# Antenna_Board_v4.net
KiCad netlist of a schematic drawn in EAGLE
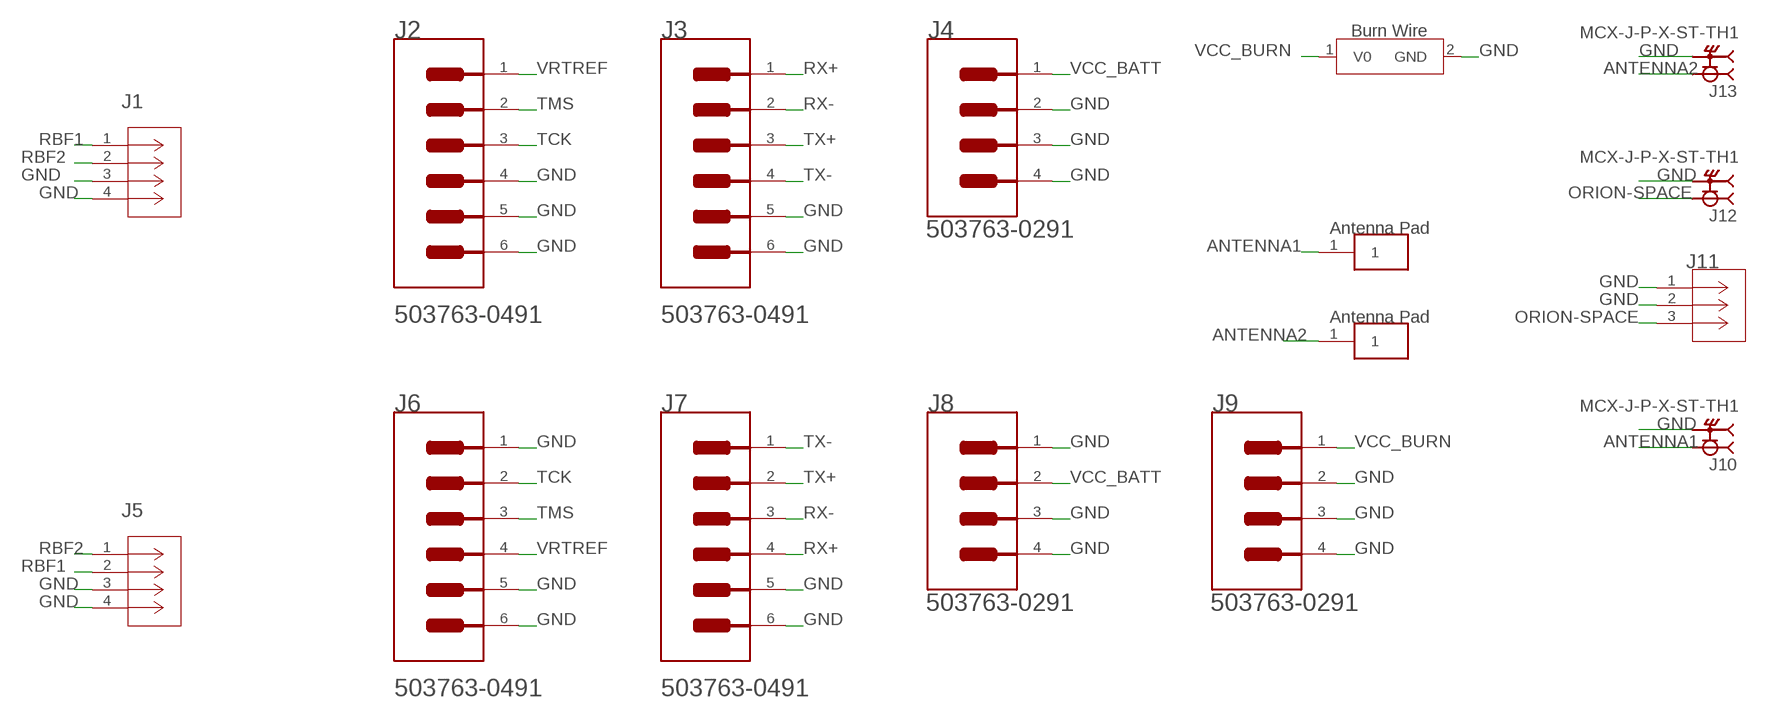
[diagram p0: schematic, sheet 1]

(export (version "E")
  (design (tool "Eeschema 10.0.6"))
  (components
    (comp (ref "J1")
      (value "5037630291")
      (footprint "eagle-import:CON_5037630291")
      (fields (field (name "COPYRIGHT") "Copyright (C) 2018 Accelerated Designs. All rights reserved"))
      (libsource (lib "eagle-import") (part "5037630291"))
    )
    (comp (ref "J2")
      (value "MOLEX_503763-0491MOLEX_503763-0491_0_0")
      (footprint "eagle-import:MOLEX_503763-0491_0")
      (fields
        (field (name "DIGIKEY_PART_NUMBER") "WM10655CT-ND")
        (field (name "MF") "Molex")
        (field (name "MOUSER_PART_NUMBER") "538-503763-0491")
      )
      (libsource (lib "eagle-import") (part "MOLEX_503763-0491MOLEX_503763-0491_0_0"))
    )
    (comp (ref "J3")
      (value "MOLEX_503763-0491MOLEX_503763-0491_0_0")
      (footprint "eagle-import:MOLEX_503763-0491_0")
      (fields
        (field (name "DIGIKEY_PART_NUMBER") "WM10655CT-ND")
        (field (name "MF") "Molex")
        (field (name "MOUSER_PART_NUMBER") "538-503763-0491")
      )
      (libsource (lib "eagle-import") (part "MOLEX_503763-0491MOLEX_503763-0491_0_0"))
    )
    (comp (ref "J4")
      (value "MOLEX_503763-0291MOLEX_503763-0291_0_0")
      (footprint "eagle-import:MOLEX_503763-0291_0")
      (fields
        (field (name "DIGIKEY_PART_NUMBER") "WM10654CT-ND")
        (field (name "MF") "Molex")
        (field (name "MOUSER_PART_NUMBER") "538-503763-0291")
      )
      (libsource (lib "eagle-import") (part "MOLEX_503763-0291MOLEX_503763-0291_0_0"))
    )
    (comp (ref "J5")
      (value "5037630291")
      (footprint "eagle-import:CON_5037630291")
      (fields (field (name "COPYRIGHT") "Copyright (C) 2018 Accelerated Designs. All rights reserved"))
      (libsource (lib "eagle-import") (part "5037630291"))
    )
    (comp (ref "J6")
      (value "MOLEX_503763-0491MOLEX_503763-0491_0_0")
      (footprint "eagle-import:MOLEX_503763-0491_0")
      (fields
        (field (name "DIGIKEY_PART_NUMBER") "WM10655CT-ND")
        (field (name "MF") "Molex")
        (field (name "MOUSER_PART_NUMBER") "538-503763-0491")
      )
      (libsource (lib "eagle-import") (part "MOLEX_503763-0491MOLEX_503763-0491_0_0"))
    )
    (comp (ref "J7")
      (value "MOLEX_503763-0491MOLEX_503763-0491_0_0")
      (footprint "eagle-import:MOLEX_503763-0491_0")
      (fields
        (field (name "DIGIKEY_PART_NUMBER") "WM10655CT-ND")
        (field (name "MF") "Molex")
        (field (name "MOUSER_PART_NUMBER") "538-503763-0491")
      )
      (libsource (lib "eagle-import") (part "MOLEX_503763-0491MOLEX_503763-0491_0_0"))
    )
    (comp (ref "J8")
      (value "MOLEX_503763-0291MOLEX_503763-0291_0_0")
      (footprint "eagle-import:MOLEX_503763-0291_0")
      (fields
        (field (name "DIGIKEY_PART_NUMBER") "WM10654CT-ND")
        (field (name "MF") "Molex")
        (field (name "MOUSER_PART_NUMBER") "538-503763-0291")
      )
      (libsource (lib "eagle-import") (part "MOLEX_503763-0291MOLEX_503763-0291_0_0"))
    )
    (comp (ref "J9")
      (value "MOLEX_503763-0291MOLEX_503763-0291_0_0")
      (footprint "eagle-import:MOLEX_503763-0291_0")
      (fields
        (field (name "DIGIKEY_PART_NUMBER") "WM10654CT-ND")
        (field (name "MF") "Molex")
        (field (name "MOUSER_PART_NUMBER") "538-503763-0291")
      )
      (libsource (lib "eagle-import") (part "MOLEX_503763-0291MOLEX_503763-0291_0_0"))
    )
    (comp (ref "J10")
      (value "MCX-J-P-X-ST-TH1")
      (footprint "eagle-import:SAMTEC_MCX-J-P-X-ST-TH1")
      (fields
        (field (name "DIGI-KEY_PART_NUMBER") "SAM8944-ND")
        (field (name "MF") "Samtec")
        (field (name "MP") "MCX-J-P-H-ST-TH1")
      )
      (libsource (lib "eagle-import") (part "MCX-J-P-X-ST-TH1"))
    )
    (comp (ref "J11")
      (value "U.FL-R-SMT-1(01)")
      (footprint "eagle-import:CONN_-SMT-1(01)")
      (fields (field (name "COPYRIGHT") "Copyright (C) 2018 Accelerated Designs. All rights reserved"))
      (libsource (lib "eagle-import") (part "U.FL-R-SMT-1(01)"))
    )
    (comp (ref "J12")
      (value "MCX-J-P-X-ST-TH1")
      (footprint "eagle-import:SAMTEC_MCX-J-P-X-ST-TH1")
      (fields
        (field (name "DIGI-KEY_PART_NUMBER") "SAM8944-ND")
        (field (name "MF") "Samtec")
        (field (name "MP") "MCX-J-P-H-ST-TH1")
      )
      (libsource (lib "eagle-import") (part "MCX-J-P-X-ST-TH1"))
    )
    (comp (ref "J13")
      (value "MCX-J-P-X-ST-TH1")
      (footprint "eagle-import:SAMTEC_MCX-J-P-X-ST-TH1")
      (fields
        (field (name "DIGI-KEY_PART_NUMBER") "SAM8944-ND")
        (field (name "MF") "Samtec")
        (field (name "MP") "MCX-J-P-H-ST-TH1")
      )
      (libsource (lib "eagle-import") (part "MCX-J-P-X-ST-TH1"))
    )
    (comp (ref "U$1")
      (value "ANTENNA_PAD+HOLES")
      (footprint "eagle-import:ANTENNA_PAD+HOLES")
      (libsource (lib "eagle-import") (part "ANTENNA_PAD+HOLES"))
    )
    (comp (ref "U$2")
      (value "ANTENNA_PAD+HOLES")
      (footprint "eagle-import:ANTENNA_PAD+HOLES")
      (libsource (lib "eagle-import") (part "ANTENNA_PAD+HOLES"))
    )
    (comp (ref "U$3")
      (value "BURNWIRE")
      (footprint "eagle-import:BURNWIRE")
      (libsource (lib "eagle-import") (part "BURNWIRE"))
    )
  )
  (nets
    (net (code "1") (name "/ANTENNA1") (class "Default")
      (node (ref "J10") (pin "1") (pinfunction "1_1") (pintype "passive"))
      (node (ref "U$1") (pin "1") (pinfunction "1_1") (pintype "bidirectional"))
    )
    (net (code "2") (name "/ANTENNA2") (class "Default")
      (node (ref "J13") (pin "1") (pinfunction "1_1") (pintype "passive"))
      (node (ref "U$2") (pin "1") (pinfunction "1_1") (pintype "bidirectional"))
    )
    (net (code "3") (name "/GND") (class "Default")
      (node (ref "J1") (pin "3") (pinfunction "3_3") (pintype "passive"))
      (node (ref "J1") (pin "4") (pinfunction "4_4") (pintype "passive"))
      (node (ref "J10") (pin "S1") (pinfunction "2_S1") (pintype "passive"))
      (node (ref "J10") (pin "S2") (pinfunction "2_S2") (pintype "passive"))
      (node (ref "J10") (pin "S3") (pinfunction "2_S3") (pintype "passive"))
      (node (ref "J10") (pin "S4") (pinfunction "2_S4") (pintype "passive"))
      (node (ref "J11") (pin "1") (pinfunction "1_1") (pintype "passive"))
      (node (ref "J11") (pin "2") (pinfunction "2_2") (pintype "passive"))
      (node (ref "J12") (pin "S1") (pinfunction "2_S1") (pintype "passive"))
      (node (ref "J12") (pin "S2") (pinfunction "2_S2") (pintype "passive"))
      (node (ref "J12") (pin "S3") (pinfunction "2_S3") (pintype "passive"))
      (node (ref "J12") (pin "S4") (pinfunction "2_S4") (pintype "passive"))
      (node (ref "J13") (pin "S1") (pinfunction "2_S1") (pintype "passive"))
      (node (ref "J13") (pin "S2") (pinfunction "2_S2") (pintype "passive"))
      (node (ref "J13") (pin "S3") (pinfunction "2_S3") (pintype "passive"))
      (node (ref "J13") (pin "S4") (pinfunction "2_S4") (pintype "passive"))
      (node (ref "J2") (pin "4") (pinfunction "4_4") (pintype "passive"))
      (node (ref "J2") (pin "5") (pinfunction "MNT_1_5") (pintype "passive"))
      (node (ref "J2") (pin "6") (pinfunction "MNT_2_6") (pintype "passive"))
      (node (ref "J3") (pin "5") (pinfunction "MNT_1_5") (pintype "passive"))
      (node (ref "J3") (pin "6") (pinfunction "MNT_2_6") (pintype "passive"))
      (node (ref "J4") (pin "2") (pinfunction "2_2") (pintype "bidirectional"))
      (node (ref "J4") (pin "3") (pinfunction "MNT_1_3") (pintype "bidirectional"))
      (node (ref "J4") (pin "4") (pinfunction "MNT_2_4") (pintype "bidirectional"))
      (node (ref "J5") (pin "3") (pinfunction "3_3") (pintype "passive"))
      (node (ref "J5") (pin "4") (pinfunction "4_4") (pintype "passive"))
      (node (ref "J6") (pin "1") (pinfunction "1_1") (pintype "passive"))
      (node (ref "J6") (pin "5") (pinfunction "MNT_1_5") (pintype "passive"))
      (node (ref "J6") (pin "6") (pinfunction "MNT_2_6") (pintype "passive"))
      (node (ref "J7") (pin "5") (pinfunction "MNT_1_5") (pintype "passive"))
      (node (ref "J7") (pin "6") (pinfunction "MNT_2_6") (pintype "passive"))
      (node (ref "J8") (pin "1") (pinfunction "1_1") (pintype "bidirectional"))
      (node (ref "J8") (pin "3") (pinfunction "MNT_1_3") (pintype "bidirectional"))
      (node (ref "J8") (pin "4") (pinfunction "MNT_2_4") (pintype "bidirectional"))
      (node (ref "J9") (pin "2") (pinfunction "2_2") (pintype "bidirectional"))
      (node (ref "J9") (pin "3") (pinfunction "MNT_1_3") (pintype "bidirectional"))
      (node (ref "J9") (pin "4") (pinfunction "MNT_2_4") (pintype "bidirectional"))
      (node (ref "U$3") (pin "2") (pinfunction "GND_2") (pintype "bidirectional"))
    )
    (net (code "4") (name "/ORION-SPACE") (class "Default")
      (node (ref "J11") (pin "3") (pinfunction "3_3") (pintype "passive"))
      (node (ref "J12") (pin "1") (pinfunction "1_1") (pintype "passive"))
    )
    (net (code "5") (name "/RBF1") (class "Default")
      (node (ref "J1") (pin "1") (pinfunction "1_1") (pintype "passive"))
      (node (ref "J5") (pin "2") (pinfunction "2_2") (pintype "passive"))
    )
    (net (code "6") (name "/RBF2") (class "Default")
      (node (ref "J1") (pin "2") (pinfunction "2_2") (pintype "passive"))
      (node (ref "J5") (pin "1") (pinfunction "1_1") (pintype "passive"))
    )
    (net (code "7") (name "/RX+") (class "Default")
      (node (ref "J3") (pin "1") (pinfunction "1_1") (pintype "passive"))
      (node (ref "J7") (pin "4") (pinfunction "4_4") (pintype "passive"))
    )
    (net (code "8") (name "/RX-") (class "Default")
      (node (ref "J3") (pin "2") (pinfunction "2_2") (pintype "passive"))
      (node (ref "J7") (pin "3") (pinfunction "3_3") (pintype "passive"))
    )
    (net (code "9") (name "/TCK") (class "Default")
      (node (ref "J2") (pin "3") (pinfunction "3_3") (pintype "passive"))
      (node (ref "J6") (pin "2") (pinfunction "2_2") (pintype "passive"))
    )
    (net (code "10") (name "/TMS") (class "Default")
      (node (ref "J2") (pin "2") (pinfunction "2_2") (pintype "passive"))
      (node (ref "J6") (pin "3") (pinfunction "3_3") (pintype "passive"))
    )
    (net (code "11") (name "/TX+") (class "Default")
      (node (ref "J3") (pin "3") (pinfunction "3_3") (pintype "passive"))
      (node (ref "J7") (pin "2") (pinfunction "2_2") (pintype "passive"))
    )
    (net (code "12") (name "/TX-") (class "Default")
      (node (ref "J3") (pin "4") (pinfunction "4_4") (pintype "passive"))
      (node (ref "J7") (pin "1") (pinfunction "1_1") (pintype "passive"))
    )
    (net (code "13") (name "/VCC_BATT") (class "Default")
      (node (ref "J4") (pin "1") (pinfunction "1_1") (pintype "bidirectional"))
      (node (ref "J8") (pin "2") (pinfunction "2_2") (pintype "bidirectional"))
    )
    (net (code "14") (name "/VCC_BURN") (class "Default")
      (node (ref "J9") (pin "1") (pinfunction "1_1") (pintype "bidirectional"))
      (node (ref "U$3") (pin "1") (pinfunction "V0_1") (pintype "bidirectional"))
    )
    (net (code "15") (name "/VRTREF") (class "Default")
      (node (ref "J2") (pin "1") (pinfunction "1_1") (pintype "passive"))
      (node (ref "J6") (pin "4") (pinfunction "4_4") (pintype "passive"))
    )
  )
)
